# autism_ray_board.net
KiCad netlist of a schematic drawn in EAGLE
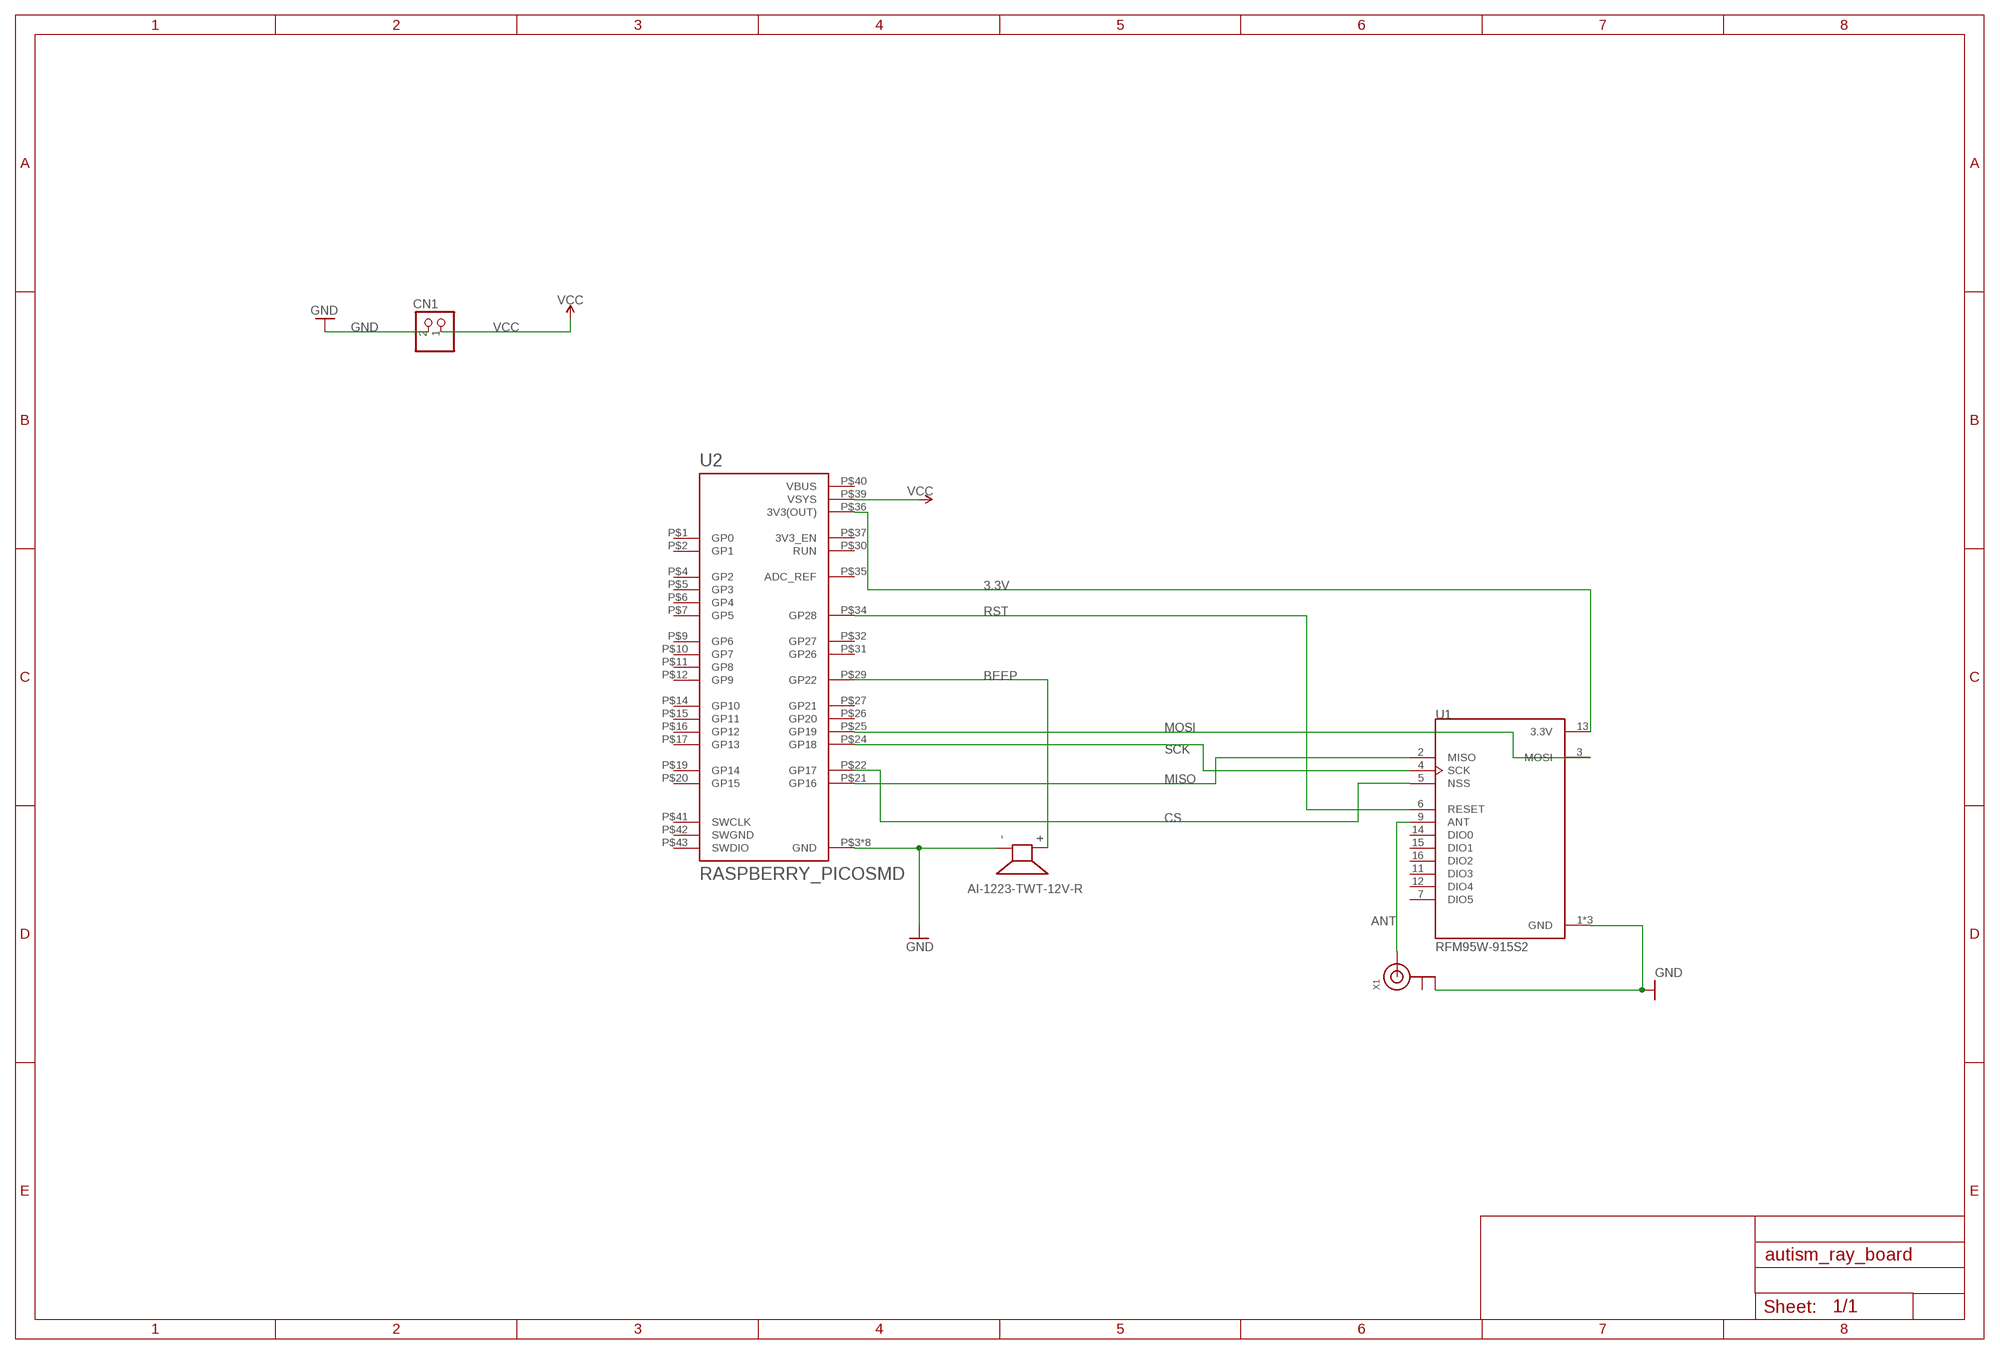
[diagram p0: schematic, sheet 1]

(export (version "E")
  (design (tool "Eeschema 10.0.6"))
  (components
    (comp (ref "CN1")
      (value "JST_2PIN-SMT-RA")
      (footprint "eagle-import:JST-PH-2-SMT-RA")
      (libsource (lib "eagle-import") (part "JST_2PIN-SMT-RA"))
    )
    (comp (ref "LS1")
      (value "AI-1223-TWT-12V-R")
      (footprint "eagle-import:XDCR_AI-1223-TWT-12V-R")
      (fields (field (name "MF") "PUI Audio,"))
      (libsource (lib "eagle-import") (part "AI-1223-TWT-12V-R"))
    )
    (comp (ref "U1")
      (value "RFM95W-915S2")
      (footprint "eagle-import:XCVR_RFM95W-915S2")
      (fields (field (name "MF") "RF Solutions"))
      (libsource (lib "eagle-import") (part "RFM95W-915S2"))
    )
    (comp (ref "U2")
      (value "RASPBERRY_PICOSMD")
      (footprint "eagle-import:PICO-PKG-SMD")
      (libsource (lib "eagle-import") (part "RASPBERRY_PICOSMD"))
    )
    (comp (ref "X1")
      (value "ANTENNA_U.FL")
      (footprint "eagle-import:U.FL")
      (libsource (lib "eagle-import") (part "ANTENNA_U.FL"))
    )
  )
  (nets
    (net (code "1") (name "/3.3V") (class "Default")
      (node (ref "U1") (pin "13") (pinfunction "3.3V_13") (pintype "power_in"))
      (node (ref "U2") (pin "P$36") (pinfunction "3V3(OUT)_P$36") (pintype "power_in"))
    )
    (net (code "2") (name "/ANT") (class "Default")
      (node (ref "U1") (pin "9") (pinfunction "ANT_9") (pintype "bidirectional"))
      (node (ref "X1") (pin "3") (pinfunction "SIGNAL_3") (pintype "passive"))
    )
    (net (code "3") (name "/BEEP") (class "Default")
      (node (ref "LS1") (pin "P") (pinfunction "+_P") (pintype "passive"))
      (node (ref "U2") (pin "P$29") (pinfunction "GP22_P$29") (pintype "bidirectional"))
    )
    (net (code "4") (name "/CS") (class "Default")
      (node (ref "U1") (pin "5") (pinfunction "NSS_5") (pintype "input"))
      (node (ref "U2") (pin "P$22") (pinfunction "GP17_P$22") (pintype "bidirectional"))
    )
    (net (code "5") (name "/MISO") (class "Default")
      (node (ref "U1") (pin "2") (pinfunction "MISO_2") (pintype "input"))
      (node (ref "U2") (pin "P$21") (pinfunction "GP16_P$21") (pintype "bidirectional"))
    )
    (net (code "6") (name "/MOSI") (class "Default")
      (node (ref "U1") (pin "3") (pinfunction "MOSI_3") (pintype "output"))
      (node (ref "U2") (pin "P$25") (pinfunction "GP19_P$25") (pintype "bidirectional"))
    )
    (net (code "7") (name "/RST") (class "Default")
      (node (ref "U1") (pin "6") (pinfunction "RESET_6") (pintype "bidirectional"))
      (node (ref "U2") (pin "P$34") (pinfunction "GP28_P$34") (pintype "bidirectional"))
    )
    (net (code "8") (name "/SCK") (class "Default")
      (node (ref "U1") (pin "4") (pinfunction "SCK_4") (pintype "input"))
      (node (ref "U2") (pin "P$24") (pinfunction "GP18_P$24") (pintype "bidirectional"))
    )
    (net (code "9") (name "/SWGND") (class "Default")
      (node (ref "U2") (pin "P$42") (pinfunction "SWGND_P$42") (pintype "power_in"))
    )
    (net (code "10") (name "/VBUS") (class "Default")
      (node (ref "U2") (pin "P$40") (pinfunction "VBUS_P$40") (pintype "power_in"))
    )
    (net (code "11") (name "GND") (class "Default")
      (node (ref "CN1") (pin "2") (pinfunction "1_2") (pintype "passive"))
      (node (ref "LS1") (pin "N") (pinfunction "-_N") (pintype "passive"))
      (node (ref "U1") (pin "1") (pinfunction "GND_1") (pintype "power_in"))
      (node (ref "U1") (pin "10") (pinfunction "GND_10") (pintype "power_in"))
      (node (ref "U1") (pin "8") (pinfunction "GND_8") (pintype "power_in"))
      (node (ref "U2") (pin "P$13") (pinfunction "GND_P$13") (pintype "power_in"))
      (node (ref "U2") (pin "P$18") (pinfunction "GND_P$18") (pintype "power_in"))
      (node (ref "U2") (pin "P$23") (pinfunction "GND_P$23") (pintype "power_in"))
      (node (ref "U2") (pin "P$28") (pinfunction "GND_P$28") (pintype "power_in"))
      (node (ref "U2") (pin "P$3") (pinfunction "GND_P$3") (pintype "power_in"))
      (node (ref "U2") (pin "P$33") (pinfunction "GND_P$33") (pintype "power_in"))
      (node (ref "U2") (pin "P$38") (pinfunction "GND_P$38") (pintype "power_in"))
      (node (ref "U2") (pin "P$8") (pinfunction "GND_P$8") (pintype "power_in"))
      (node (ref "X1") (pin "2") (pinfunction "GND_2") (pintype "passive"))
    )
    (net (code "12") (name "VCC") (class "Default")
      (node (ref "CN1") (pin "1") (pinfunction "2_1") (pintype "passive"))
      (node (ref "U2") (pin "P$39") (pinfunction "VSYS_P$39") (pintype "power_in"))
    )
    (net (code "13") (name "unconnected-(U1-DIO0-Pad14)") (class "Default")
      (node (ref "U1") (pin "14") (pinfunction "DIO0_14") (pintype "bidirectional"))
    )
    (net (code "14") (name "unconnected-(U1-DIO1-Pad15)") (class "Default")
      (node (ref "U1") (pin "15") (pinfunction "DIO1_15") (pintype "bidirectional"))
    )
    (net (code "15") (name "unconnected-(U1-DIO2-Pad16)") (class "Default")
      (node (ref "U1") (pin "16") (pinfunction "DIO2_16") (pintype "bidirectional"))
    )
    (net (code "16") (name "unconnected-(U1-DIO3-Pad11)") (class "Default")
      (node (ref "U1") (pin "11") (pinfunction "DIO3_11") (pintype "bidirectional"))
    )
    (net (code "17") (name "unconnected-(U1-DIO4-Pad12)") (class "Default")
      (node (ref "U1") (pin "12") (pinfunction "DIO4_12") (pintype "bidirectional"))
    )
    (net (code "18") (name "unconnected-(U1-DIO5-Pad7)") (class "Default")
      (node (ref "U1") (pin "7") (pinfunction "DIO5_7") (pintype "bidirectional"))
    )
    (net (code "19") (name "unconnected-(U2-3V3_EN-PadP$37)") (class "Default")
      (node (ref "U2") (pin "P$37") (pinfunction "3V3_EN_P$37") (pintype "input"))
    )
    (net (code "20") (name "unconnected-(U2-ADC_REF-PadP$35)") (class "Default")
      (node (ref "U2") (pin "P$35") (pinfunction "ADC_REF_P$35") (pintype "input"))
    )
    (net (code "21") (name "unconnected-(U2-GP0-PadP$1)") (class "Default")
      (node (ref "U2") (pin "P$1") (pinfunction "GP0_P$1") (pintype "bidirectional"))
    )
    (net (code "22") (name "unconnected-(U2-GP1-PadP$2)") (class "Default")
      (node (ref "U2") (pin "P$2") (pinfunction "GP1_P$2") (pintype "bidirectional"))
    )
    (net (code "23") (name "unconnected-(U2-GP2-PadP$4)") (class "Default")
      (node (ref "U2") (pin "P$4") (pinfunction "GP2_P$4") (pintype "bidirectional"))
    )
    (net (code "24") (name "unconnected-(U2-GP3-PadP$5)") (class "Default")
      (node (ref "U2") (pin "P$5") (pinfunction "GP3_P$5") (pintype "bidirectional"))
    )
    (net (code "25") (name "unconnected-(U2-GP4-PadP$6)") (class "Default")
      (node (ref "U2") (pin "P$6") (pinfunction "GP4_P$6") (pintype "bidirectional"))
    )
    (net (code "26") (name "unconnected-(U2-GP5-PadP$7)") (class "Default")
      (node (ref "U2") (pin "P$7") (pinfunction "GP5_P$7") (pintype "bidirectional"))
    )
    (net (code "27") (name "unconnected-(U2-GP6-PadP$9)") (class "Default")
      (node (ref "U2") (pin "P$9") (pinfunction "GP6_P$9") (pintype "bidirectional"))
    )
    (net (code "28") (name "unconnected-(U2-GP7-PadP$10)") (class "Default")
      (node (ref "U2") (pin "P$10") (pinfunction "GP7_P$10") (pintype "bidirectional"))
    )
    (net (code "29") (name "unconnected-(U2-GP8-PadP$11)") (class "Default")
      (node (ref "U2") (pin "P$11") (pinfunction "GP8_P$11") (pintype "bidirectional"))
    )
    (net (code "30") (name "unconnected-(U2-GP9-PadP$12)") (class "Default")
      (node (ref "U2") (pin "P$12") (pinfunction "GP9_P$12") (pintype "bidirectional"))
    )
    (net (code "31") (name "unconnected-(U2-GP10-PadP$14)") (class "Default")
      (node (ref "U2") (pin "P$14") (pinfunction "GP10_P$14") (pintype "bidirectional"))
    )
    (net (code "32") (name "unconnected-(U2-GP11-PadP$15)") (class "Default")
      (node (ref "U2") (pin "P$15") (pinfunction "GP11_P$15") (pintype "bidirectional"))
    )
    (net (code "33") (name "unconnected-(U2-GP12-PadP$16)") (class "Default")
      (node (ref "U2") (pin "P$16") (pinfunction "GP12_P$16") (pintype "bidirectional"))
    )
    (net (code "34") (name "unconnected-(U2-GP13-PadP$17)") (class "Default")
      (node (ref "U2") (pin "P$17") (pinfunction "GP13_P$17") (pintype "bidirectional"))
    )
    (net (code "35") (name "unconnected-(U2-GP14-PadP$19)") (class "Default")
      (node (ref "U2") (pin "P$19") (pinfunction "GP14_P$19") (pintype "bidirectional"))
    )
    (net (code "36") (name "unconnected-(U2-GP15-PadP$20)") (class "Default")
      (node (ref "U2") (pin "P$20") (pinfunction "GP15_P$20") (pintype "bidirectional"))
    )
    (net (code "37") (name "unconnected-(U2-GP20-PadP$26)") (class "Default")
      (node (ref "U2") (pin "P$26") (pinfunction "GP20_P$26") (pintype "bidirectional"))
    )
    (net (code "38") (name "unconnected-(U2-GP21-PadP$27)") (class "Default")
      (node (ref "U2") (pin "P$27") (pinfunction "GP21_P$27") (pintype "bidirectional"))
    )
    (net (code "39") (name "unconnected-(U2-GP26-PadP$31)") (class "Default")
      (node (ref "U2") (pin "P$31") (pinfunction "GP26_P$31") (pintype "bidirectional"))
    )
    (net (code "40") (name "unconnected-(U2-GP27-PadP$32)") (class "Default")
      (node (ref "U2") (pin "P$32") (pinfunction "GP27_P$32") (pintype "bidirectional"))
    )
    (net (code "41") (name "unconnected-(U2-RUN-PadP$30)") (class "Default")
      (node (ref "U2") (pin "P$30") (pinfunction "RUN_P$30") (pintype "input"))
    )
    (net (code "42") (name "unconnected-(U2-SWCLK-PadP$41)") (class "Default")
      (node (ref "U2") (pin "P$41") (pinfunction "SWCLK_P$41") (pintype "input"))
    )
    (net (code "43") (name "unconnected-(U2-SWDIO-PadP$43)") (class "Default")
      (node (ref "U2") (pin "P$43") (pinfunction "SWDIO_P$43") (pintype "bidirectional"))
    )
    (net (code "44") (name "unconnected-(X1-GND-Pad1)") (class "Default")
      (node (ref "X1") (pin "1") (pinfunction "GND_1") (pintype "passive"))
    )
  )
)
